# controller16.net
KiCad netlist of a schematic drawn in EAGLE
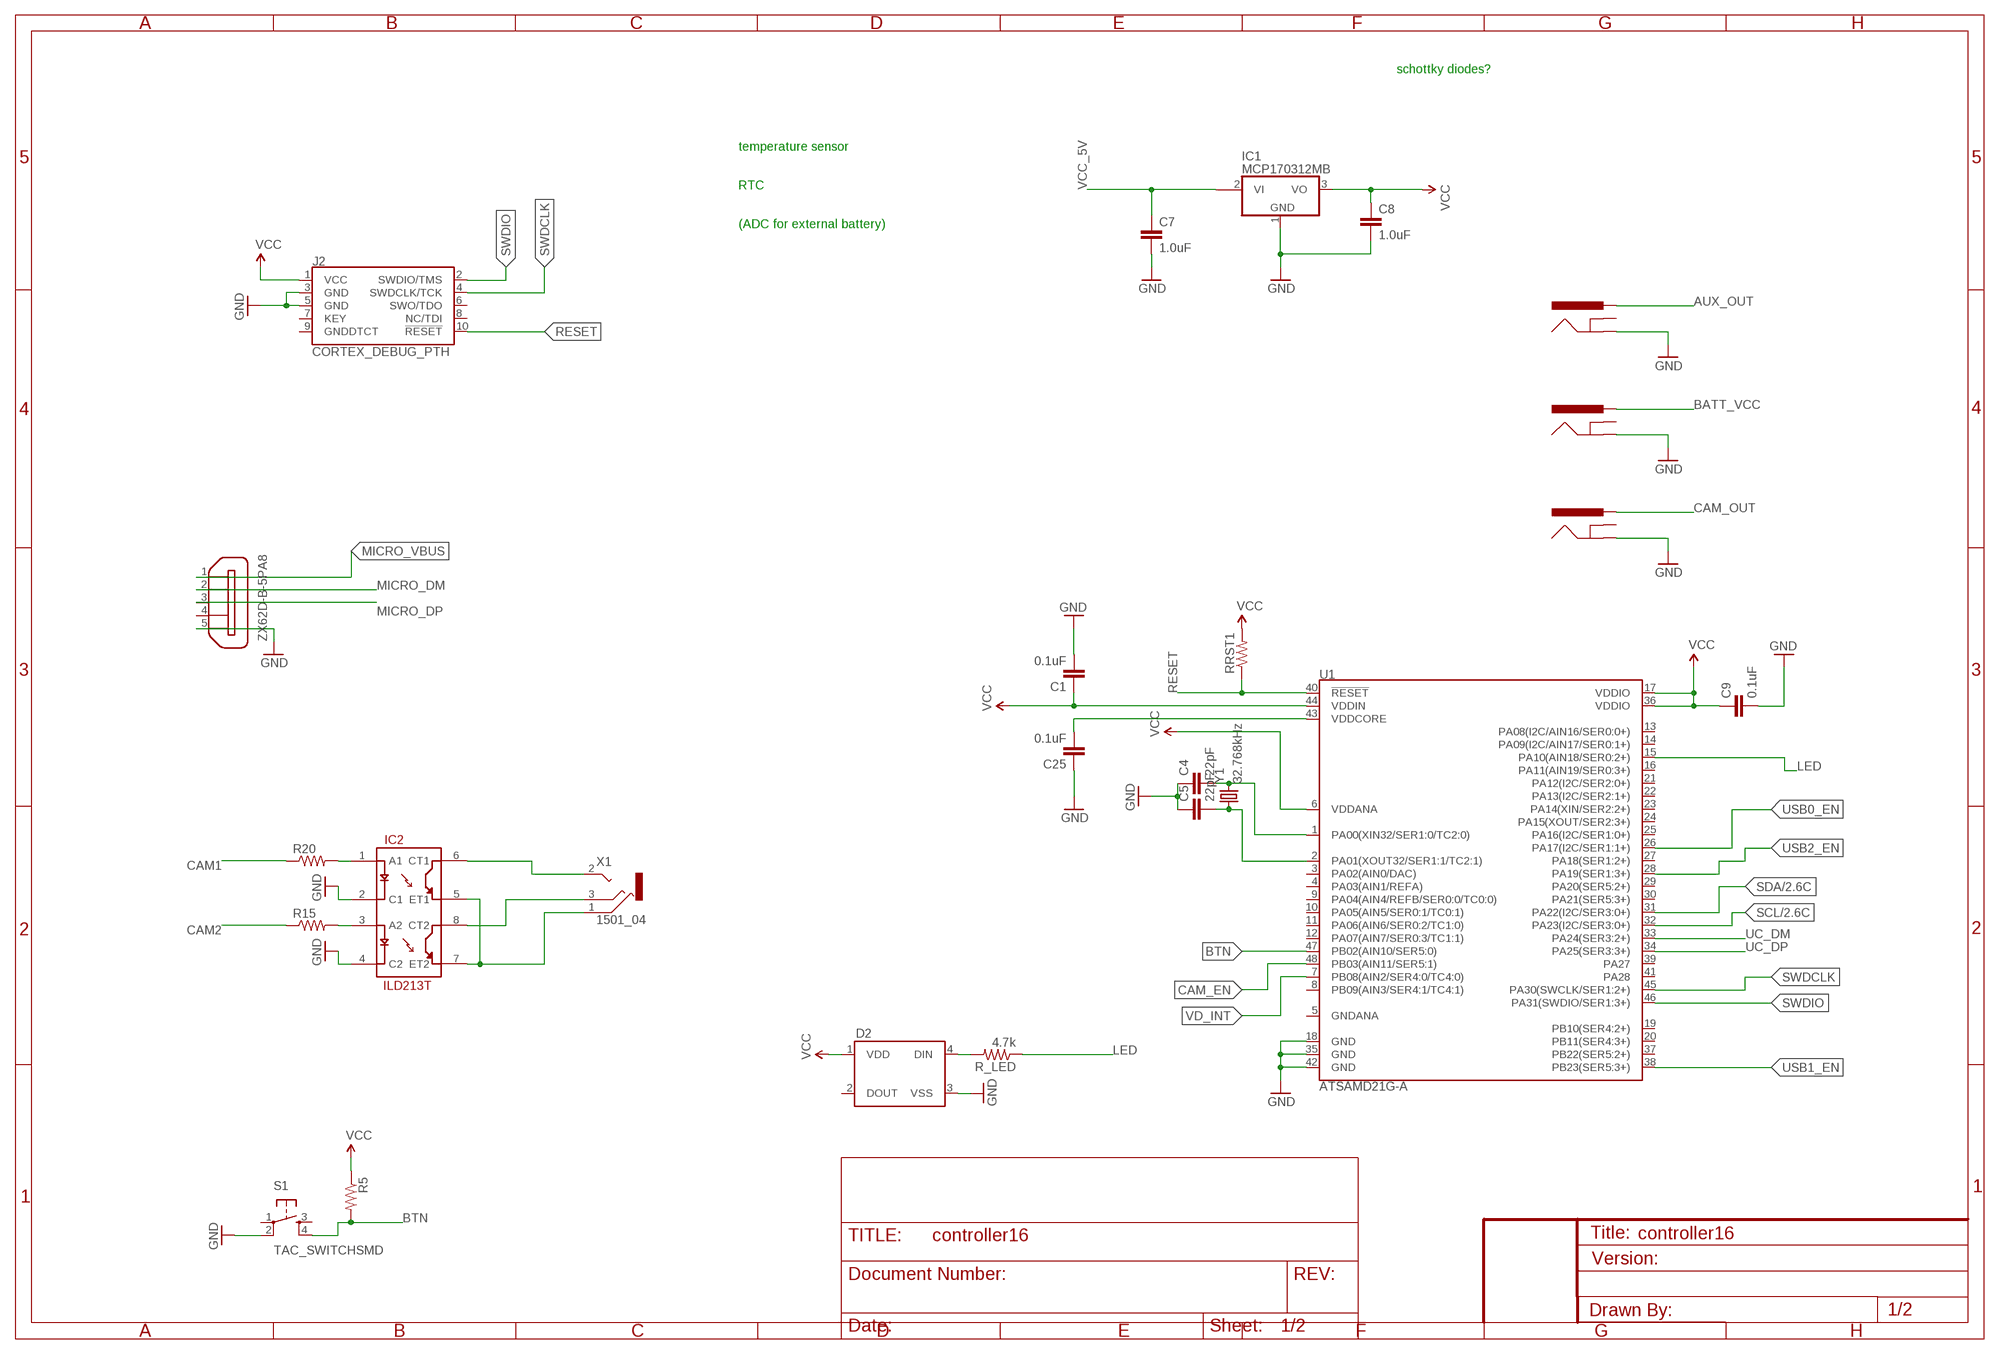
[diagram p0: schematic, sheet 1]
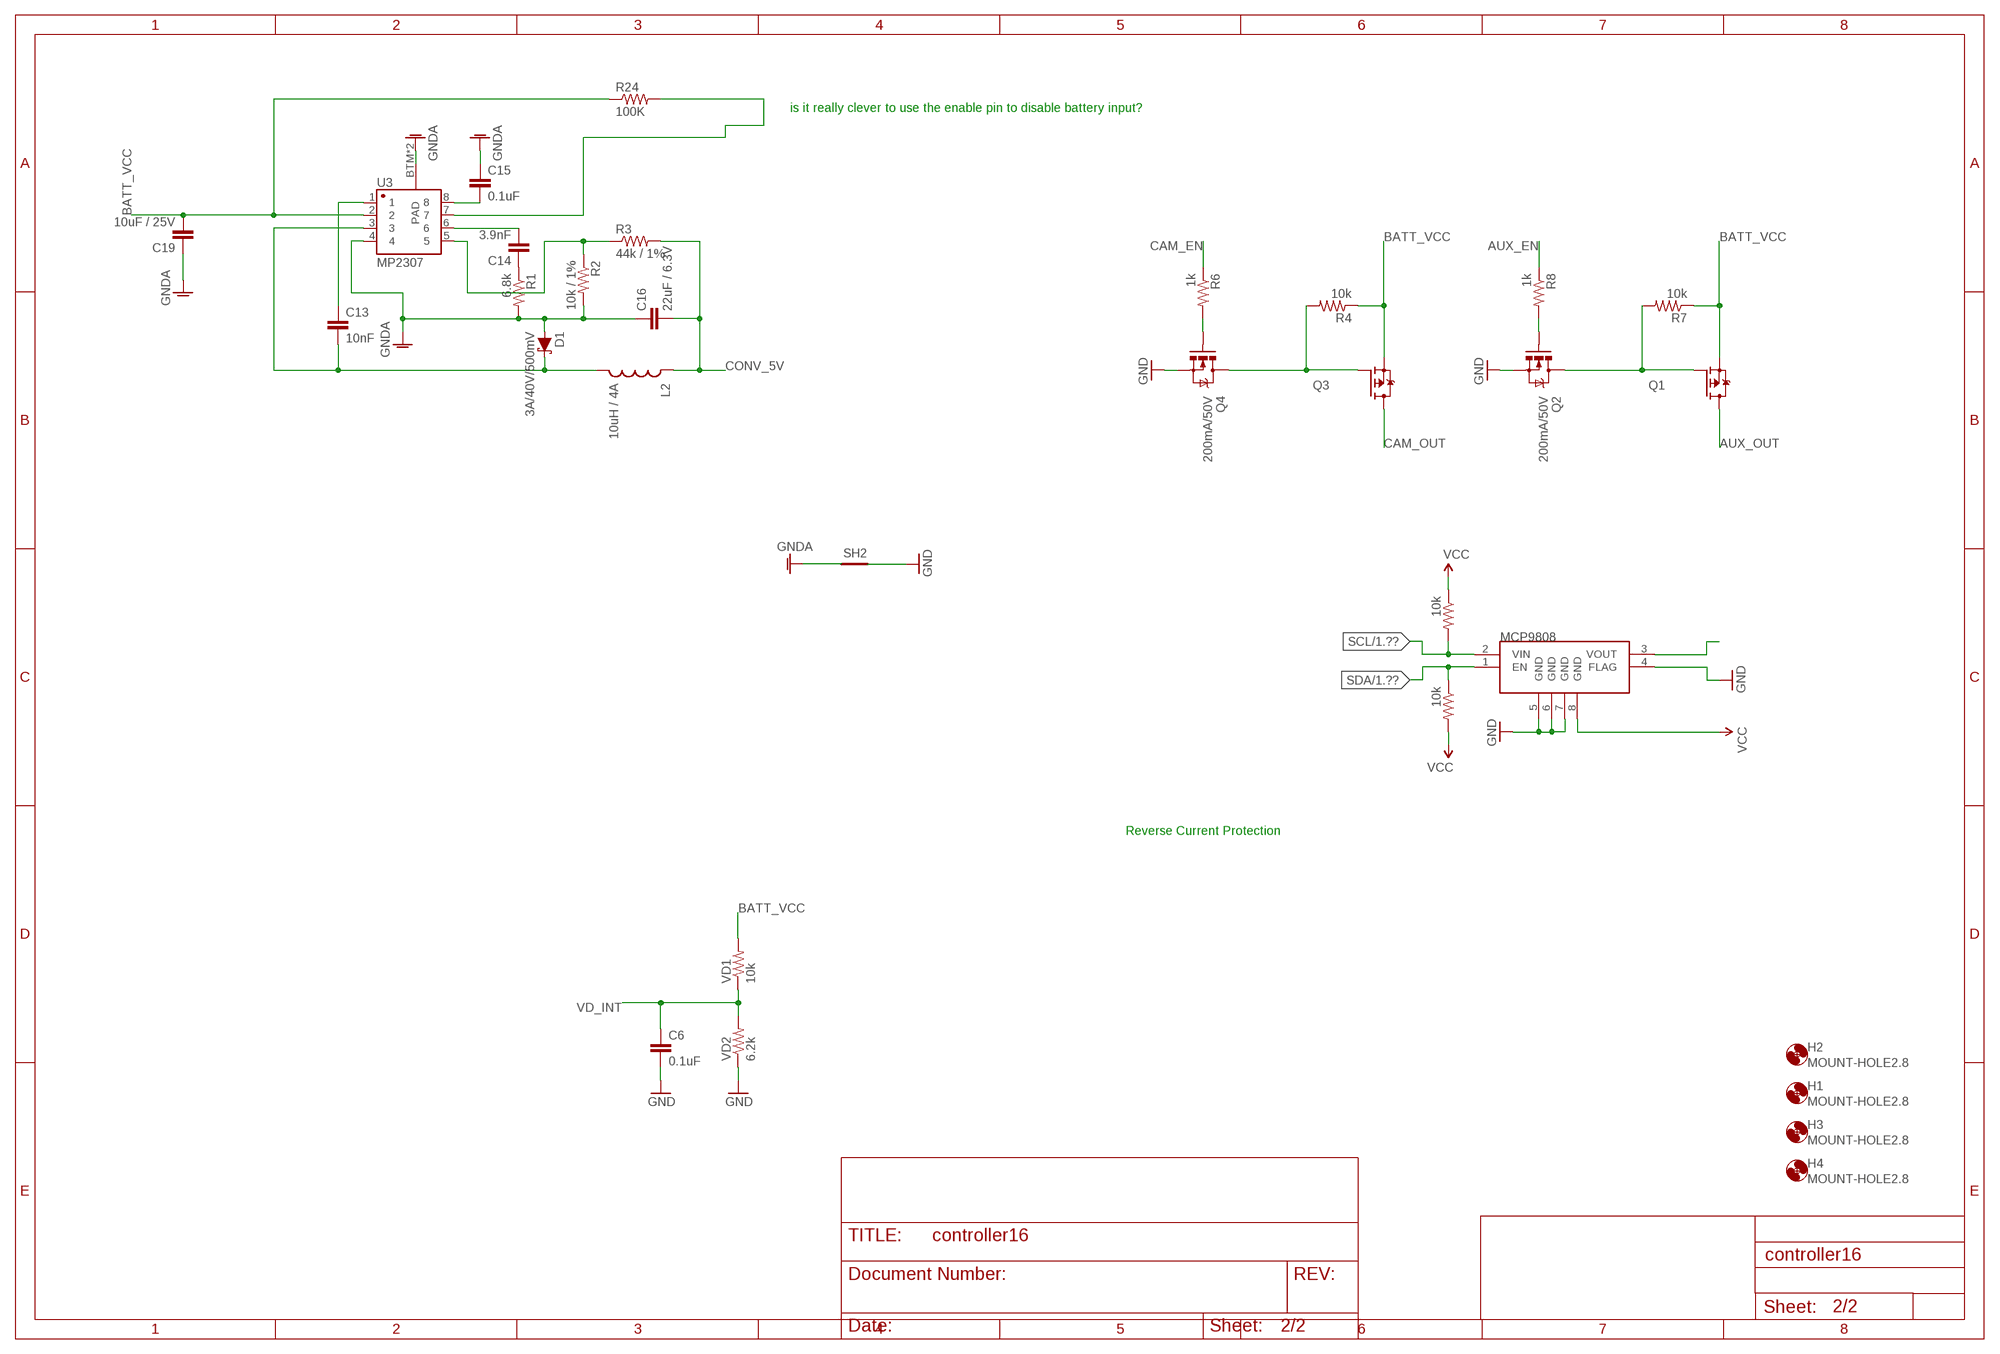
[diagram p1: schematic, sheet 2]

(export (version "E")
  (design (tool "Eeschema 10.0.6"))
  (components
    (comp (ref "C6")
      (value "0.1uF")
      (footprint "eagle-import:1206")
      (libsource (lib "eagle-import") (part "CAP1206"))
    )
    (comp (ref "C13")
      (value "10nF")
      (footprint "eagle-import:0805")
      (libsource (lib "eagle-import") (part "CAP0805"))
    )
    (comp (ref "C14")
      (value "3.9nF")
      (footprint "eagle-import:1206")
      (libsource (lib "eagle-import") (part "CAP1206"))
    )
    (comp (ref "C15")
      (value "0.1uF")
      (footprint "eagle-import:1206")
      (libsource (lib "eagle-import") (part "CAP1206"))
    )
    (comp (ref "C16")
      (value "22uF / 6.3V")
      (footprint "eagle-import:1210")
      (libsource (lib "eagle-import") (part "CAP1210"))
    )
    (comp (ref "C19")
      (value "10uF / 25V")
      (footprint "eagle-import:1210")
      (libsource (lib "eagle-import") (part "CAP1210"))
    )
    (comp (ref "D1")
      (value "3A/40V/500mV")
      (footprint "eagle-import:SMA-DIODE")
      (libsource (lib "eagle-import") (part "DIODE-SCHOTTKY-B340A"))
    )
    (comp (ref "H1")
      (value "MOUNT-HOLE2.8")
      (footprint "eagle-import:2,8")
      (libsource (lib "eagle-import") (part "MOUNT-HOLE2.8"))
    )
    (comp (ref "H2")
      (value "MOUNT-HOLE2.8")
      (footprint "eagle-import:2,8")
      (libsource (lib "eagle-import") (part "MOUNT-HOLE2.8"))
    )
    (comp (ref "H3")
      (value "MOUNT-HOLE2.8")
      (footprint "eagle-import:2,8")
      (libsource (lib "eagle-import") (part "MOUNT-HOLE2.8"))
    )
    (comp (ref "H4")
      (value "MOUNT-HOLE2.8")
      (footprint "eagle-import:2,8")
      (libsource (lib "eagle-import") (part "MOUNT-HOLE2.8"))
    )
    (comp (ref "L2")
      (value "10uH / 4A")
      (footprint "eagle-import:SRU1038")
      (libsource (lib "eagle-import") (part "INDUCTORSRU1038"))
    )
    (comp (ref "MCP9808")
      (value "V_REG_MIC5216")
      (footprint "eagle-import:MSOP8")
      (libsource (lib "eagle-import") (part "V_REG_MIC5216"))
    )
    (comp (ref "Q1")
      (value "FDD4141TO252")
      (footprint "eagle-import:TO252")
      (libsource (lib "eagle-import") (part "FDD4141TO252"))
    )
    (comp (ref "Q2")
      (value "200mA/50V")
      (footprint "eagle-import:SOT23-3")
      (libsource (lib "eagle-import") (part "MOSFET-NCHANNELBSS138"))
    )
    (comp (ref "Q3")
      (value "FDD4141TO252")
      (footprint "eagle-import:TO252")
      (libsource (lib "eagle-import") (part "FDD4141TO252"))
    )
    (comp (ref "Q4")
      (value "200mA/50V")
      (footprint "eagle-import:SOT23-3")
      (libsource (lib "eagle-import") (part "MOSFET-NCHANNELBSS138"))
    )
    (comp (ref "R1")
      (value "6.8k")
      (footprint "eagle-import:1206")
      (libsource (lib "eagle-import") (part "SparkFun-Resistors_RESISTOR1206"))
    )
    (comp (ref "R2")
      (value "10k / 1%")
      (footprint "eagle-import:1206")
      (libsource (lib "eagle-import") (part "SparkFun-Resistors_RESISTOR1206"))
    )
    (comp (ref "R3")
      (value "44k / 1%")
      (footprint "eagle-import:1206")
      (libsource (lib "eagle-import") (part "SparkFun-Resistors_RESISTOR1206"))
    )
    (comp (ref "R4")
      (value "10k")
      (footprint "eagle-import:0805")
      (libsource (lib "eagle-import") (part "SparkFun-Resistors_RESISTOR0805-RES"))
    )
    (comp (ref "R6")
      (value "1k")
      (footprint "eagle-import:0805")
      (libsource (lib "eagle-import") (part "SparkFun-Resistors_RESISTOR0805-RES"))
    )
    (comp (ref "R7")
      (value "10k")
      (footprint "eagle-import:0805")
      (libsource (lib "eagle-import") (part "SparkFun-Resistors_RESISTOR0805-RES"))
    )
    (comp (ref "R8")
      (value "1k")
      (footprint "eagle-import:0805")
      (libsource (lib "eagle-import") (part "SparkFun-Resistors_RESISTOR0805-RES"))
    )
    (comp (ref "R24")
      (value "100K")
      (footprint "eagle-import:1206")
      (libsource (lib "eagle-import") (part "SparkFun-Resistors_RESISTOR1206"))
    )
    (comp (ref "R_I2C_1")
      (value "10k")
      (footprint "eagle-import:0805")
      (libsource (lib "eagle-import") (part "RESISTOR0805-RES"))
    )
    (comp (ref "R_I2C_2")
      (value "10k")
      (footprint "eagle-import:0805")
      (libsource (lib "eagle-import") (part "RESISTOR0805-RES"))
    )
    (comp (ref "SH2")
      (value "SHORT-HT5")
      (footprint "eagle-import:SHORT_TOP-50")
      (libsource (lib "eagle-import") (part "SHORT-HT5"))
    )
    (comp (ref "U3")
      (value "MP2307")
      (footprint "eagle-import:SO08")
      (libsource (lib "eagle-import") (part "GENERIC-SOIC8MSGEQ7N-FILTER"))
    )
    (comp (ref "VD1")
      (value "10k")
      (footprint "eagle-import:1206")
      (libsource (lib "eagle-import") (part "RESISTOR1206"))
    )
    (comp (ref "VD2")
      (value "6.2k")
      (footprint "eagle-import:1206")
      (libsource (lib "eagle-import") (part "RESISTOR1206"))
    )
    (comp (ref "C1")
      (value "0.1uF")
      (footprint "eagle-import:0805")
      (libsource (lib "eagle-import") (part "1.0UF-0805-25V-10%"))
    )
    (comp (ref "C4")
      (value "22pF")
      (footprint "eagle-import:0805")
      (libsource (lib "eagle-import") (part "SparkFun-Passives_CAP0805"))
    )
    (comp (ref "C5")
      (value "22pF")
      (footprint "eagle-import:0805")
      (libsource (lib "eagle-import") (part "SparkFun-Passives_CAP0805"))
    )
    (comp (ref "C7")
      (value "1.0uF")
      (footprint "eagle-import:1206")
      (libsource (lib "eagle-import") (part "1.0UF-1206-50V-10%"))
    )
    (comp (ref "C8")
      (value "1.0uF")
      (footprint "eagle-import:1206")
      (libsource (lib "eagle-import") (part "1.0UF-1206-50V-10%"))
    )
    (comp (ref "C9")
      (value "0.1uF")
      (footprint "eagle-import:0805")
      (libsource (lib "eagle-import") (part "1.0UF-0805-25V-10%"))
    )
    (comp (ref "C25")
      (value "0.1uF")
      (footprint "eagle-import:0805")
      (libsource (lib "eagle-import") (part "1.0UF-0805-25V-10%"))
    )
    (comp (ref "D2")
      (value "WS2812B")
      (footprint "eagle-import:WS2812B")
      (libsource (lib "eagle-import") (part "WS2812B"))
    )
    (comp (ref "IC1")
      (value "MCP170312MB")
      (footprint "eagle-import:SOT89")
      (libsource (lib "eagle-import") (part "MCP1703MB12"))
    )
    (comp (ref "IC2")
      (value "ILD213T")
      (footprint "eagle-import:SO08")
      (libsource (lib "eagle-import") (part "ILD213T"))
    )
    (comp (ref "J1")
      (value "POWER_JACKPTH_BREAD")
      (footprint "eagle-import:POWER_JACK_PTH_BREAD")
      (libsource (lib "eagle-import") (part "POWER_JACKPTH_BREAD"))
    )
    (comp (ref "J2")
      (value "CORTEX_DEBUG_PTH")
      (footprint "eagle-import:2X5-PTH-1.27MM")
      (libsource (lib "eagle-import") (part "CORTEX_DEBUG_PTH"))
    )
    (comp (ref "J3")
      (value "POWER_JACKPTH_BREAD")
      (footprint "eagle-import:POWER_JACK_PTH_BREAD")
      (libsource (lib "eagle-import") (part "POWER_JACKPTH_BREAD"))
    )
    (comp (ref "J4")
      (value "POWER_JACKPTH_BREAD")
      (footprint "eagle-import:POWER_JACK_PTH_BREAD")
      (libsource (lib "eagle-import") (part "POWER_JACKPTH_BREAD"))
    )
    (comp (ref "R5")
      (value "RESISTOR0805-RES")
      (footprint "eagle-import:0805")
      (libsource (lib "eagle-import") (part "RESISTOR0805-RES"))
    )
    (comp (ref "R15")
      (value "RESISTOR0805-RES")
      (footprint "eagle-import:0805")
      (libsource (lib "eagle-import") (part "RESISTOR0805-RES"))
    )
    (comp (ref "R20")
      (value "RESISTOR0805-RES")
      (footprint "eagle-import:0805")
      (libsource (lib "eagle-import") (part "RESISTOR0805-RES"))
    )
    (comp (ref "RRST1")
      (value "RESISTOR0805-RES")
      (footprint "eagle-import:0805")
      (libsource (lib "eagle-import") (part "RESISTOR0805-RES"))
    )
    (comp (ref "R_LED")
      (value "4.7k")
      (footprint "eagle-import:0805")
      (libsource (lib "eagle-import") (part "SparkFun-Resistors_RESISTOR0805-RES"))
    )
    (comp (ref "S1")
      (value "TAC_SWITCHSMD")
      (footprint "eagle-import:TACTILE-SWITCH-SMD")
      (libsource (lib "eagle-import") (part "TAC_SWITCHSMD"))
    )
    (comp (ref "U1")
      (value "ATSAMD21G-A")
      (footprint "eagle-import:TQFP-48")
      (libsource (lib "eagle-import") (part "ATSAMD21G-A"))
    )
    (comp (ref "X1")
      (value "1501_04")
      (footprint "eagle-import:1501_05")
      (libsource (lib "eagle-import") (part "1501_04"))
    )
    (comp (ref "X2")
      (value "ZX62D-B-5PA8")
      (footprint "eagle-import:ZX62D-B-5PA8")
      (fields (field (name "MF") "Hirose"))
      (libsource (lib "eagle-import") (part "ZX62D-B-5PA8"))
    )
    (comp (ref "Y1")
      (value "32.768kHz")
      (footprint "eagle-import:CRYSTAL-SMD-3.2X1.5MM")
      (libsource (lib "eagle-import") (part "CRYSTAL3.2X1.5MM"))
    )
  )
  (nets
    (net (code "1") (name "AUX_EN") (class "Default")
      (node (ref "R8") (pin "1") (pinfunction "1_1") (pintype "passive"))
    )
    (net (code "2") (name "AUX_OUT") (class "Default")
      (node (ref "J1") (pin "PWR") (pinfunction "PWR_PWR") (pintype "bidirectional"))
      (node (ref "Q1") (pin "3") (pinfunction "D_3") (pintype "passive"))
    )
    (net (code "3") (name "BATT_VCC") (class "Default")
      (node (ref "C19") (pin "2") (pinfunction "2_2") (pintype "passive"))
      (node (ref "J4") (pin "PWR") (pinfunction "PWR_PWR") (pintype "bidirectional"))
      (node (ref "Q1") (pin "2") (pinfunction "S_2") (pintype "passive"))
      (node (ref "Q3") (pin "2") (pinfunction "S_2") (pintype "passive"))
      (node (ref "R24") (pin "1") (pinfunction "1_1") (pintype "passive"))
      (node (ref "R4") (pin "1") (pinfunction "1_1") (pintype "passive"))
      (node (ref "R7") (pin "1") (pinfunction "1_1") (pintype "passive"))
      (node (ref "U3") (pin "2") (pinfunction "2_2") (pintype "bidirectional"))
      (node (ref "VD1") (pin "2") (pinfunction "2_2") (pintype "passive"))
    )
    (net (code "4") (name "BTN") (class "Default")
      (node (ref "R5") (pin "2") (pinfunction "2_2") (pintype "passive"))
      (node (ref "S1") (pin "4") (pinfunction "4_4") (pintype "passive"))
      (node (ref "U1") (pin "47") (pinfunction "PB02(AIN10/SER5:0)_47") (pintype "bidirectional"))
    )
    (net (code "5") (name "CAM1") (class "Default")
      (node (ref "R20") (pin "1") (pinfunction "1_1") (pintype "passive"))
    )
    (net (code "6") (name "CAM2") (class "Default")
      (node (ref "R15") (pin "1") (pinfunction "1_1") (pintype "passive"))
    )
    (net (code "7") (name "CAM_EN") (class "Default")
      (node (ref "R6") (pin "1") (pinfunction "1_1") (pintype "passive"))
      (node (ref "U1") (pin "48") (pinfunction "PB03(AIN11/SER5:1)_48") (pintype "bidirectional"))
    )
    (net (code "8") (name "CAM_OUT") (class "Default")
      (node (ref "J3") (pin "PWR") (pinfunction "PWR_PWR") (pintype "bidirectional"))
      (node (ref "Q3") (pin "3") (pinfunction "D_3") (pintype "passive"))
    )
    (net (code "9") (name "CONV_5V") (class "Default")
      (node (ref "C16") (pin "2") (pinfunction "2_2") (pintype "passive"))
      (node (ref "L2") (pin "1") (pinfunction "1_1") (pintype "passive"))
      (node (ref "R3") (pin "2") (pinfunction "2_2") (pintype "passive"))
    )
    (net (code "10") (name "GND") (class "Default")
      (node (ref "C1") (pin "2") (pinfunction "2_2") (pintype "passive"))
      (node (ref "C25") (pin "1") (pinfunction "1_1") (pintype "passive"))
      (node (ref "C4") (pin "1") (pinfunction "1_1") (pintype "passive"))
      (node (ref "C5") (pin "1") (pinfunction "1_1") (pintype "passive"))
      (node (ref "C6") (pin "2") (pinfunction "2_2") (pintype "passive"))
      (node (ref "C7") (pin "2") (pinfunction "2_2") (pintype "passive"))
      (node (ref "C8") (pin "2") (pinfunction "2_2") (pintype "passive"))
      (node (ref "C9") (pin "2") (pinfunction "2_2") (pintype "passive"))
      (node (ref "D2") (pin "3") (pinfunction "VSS_3") (pintype "power_in"))
      (node (ref "IC1") (pin "1") (pinfunction "GND_1") (pintype "passive"))
      (node (ref "IC2") (pin "2") (pinfunction "C1_2") (pintype "bidirectional"))
      (node (ref "IC2") (pin "4") (pinfunction "C2_4") (pintype "bidirectional"))
      (node (ref "J1") (pin "GND") (pinfunction "GND_GND") (pintype "bidirectional"))
      (node (ref "J2") (pin "3") (pinfunction "GND_3") (pintype "bidirectional"))
      (node (ref "J2") (pin "5") (pinfunction "GND_5") (pintype "bidirectional"))
      (node (ref "J3") (pin "GND") (pinfunction "GND_GND") (pintype "bidirectional"))
      (node (ref "J4") (pin "GND") (pinfunction "GND_GND") (pintype "bidirectional"))
      (node (ref "MCP9808") (pin "4") (pinfunction "FLAG_4") (pintype "bidirectional"))
      (node (ref "MCP9808") (pin "5") (pinfunction "GND_5") (pintype "bidirectional"))
      (node (ref "MCP9808") (pin "6") (pinfunction "GND_6") (pintype "bidirectional"))
      (node (ref "MCP9808") (pin "7") (pinfunction "GND_7") (pintype "bidirectional"))
      (node (ref "Q2") (pin "2") (pinfunction "S_2") (pintype "passive"))
      (node (ref "Q4") (pin "2") (pinfunction "S_2") (pintype "passive"))
      (node (ref "S1") (pin "2") (pinfunction "2_2") (pintype "passive"))
      (node (ref "SH2") (pin "2") (pinfunction "P$2_2") (pintype "bidirectional"))
      (node (ref "U1") (pin "18") (pinfunction "GND_18") (pintype "bidirectional"))
      (node (ref "U1") (pin "35") (pinfunction "GND_35") (pintype "bidirectional"))
      (node (ref "U1") (pin "42") (pinfunction "GND_42") (pintype "bidirectional"))
      (node (ref "VD2") (pin "1") (pinfunction "1_1") (pintype "passive"))
      (node (ref "X2") (pin "5") (pinfunction "5_5") (pintype "passive"))
    )
    (net (code "11") (name "GNDA") (class "Default")
      (node (ref "C15") (pin "1") (pinfunction "1_1") (pintype "passive"))
      (node (ref "C16") (pin "1") (pinfunction "1_1") (pintype "passive"))
      (node (ref "C19") (pin "1") (pinfunction "1_1") (pintype "passive"))
      (node (ref "D1") (pin "A") (pinfunction "A_A") (pintype "passive"))
      (node (ref "R1") (pin "2") (pinfunction "2_2") (pintype "passive"))
      (node (ref "R2") (pin "2") (pinfunction "2_2") (pintype "passive"))
      (node (ref "SH2") (pin "1") (pinfunction "P$1_1") (pintype "bidirectional"))
      (node (ref "U3") (pin "4") (pinfunction "4_4") (pintype "bidirectional"))
      (node (ref "U3") (pin "BTM") (pinfunction "PAD_BTM") (pintype "bidirectional"))
      (node (ref "U3") (pin "P$1") (pinfunction "PAD_P$1") (pintype "bidirectional"))
    )
    (net (code "12") (name "LED") (class "Default")
      (node (ref "R_LED") (pin "1") (pinfunction "1_1") (pintype "passive"))
      (node (ref "U1") (pin "15") (pinfunction "PA10(AIN18/SER0:2+)_15") (pintype "bidirectional"))
    )
    (net (code "13") (name "MICRO_DM") (class "Default")
      (node (ref "X2") (pin "2") (pinfunction "2_2") (pintype "passive"))
    )
    (net (code "14") (name "MICRO_DP") (class "Default")
      (node (ref "X2") (pin "3") (pinfunction "3_3") (pintype "passive"))
    )
    (net (code "15") (name "MICRO_VBUS") (class "Default")
      (node (ref "X2") (pin "1") (pinfunction "1_1") (pintype "passive"))
    )
    (net (code "16") (name "Net-(C13-Pad1)") (class "Default")
      (node (ref "C13") (pin "1") (pinfunction "1_1") (pintype "passive"))
      (node (ref "U3") (pin "1") (pinfunction "1_1") (pintype "bidirectional"))
    )
    (net (code "17") (name "Net-(C13-Pad2)") (class "Default")
      (node (ref "C13") (pin "2") (pinfunction "2_2") (pintype "passive"))
      (node (ref "D1") (pin "C") (pinfunction "C_C") (pintype "passive"))
      (node (ref "L2") (pin "2") (pinfunction "2_2") (pintype "passive"))
      (node (ref "U3") (pin "3") (pinfunction "3_3") (pintype "bidirectional"))
    )
    (net (code "18") (name "Net-(C14-Pad1)") (class "Default")
      (node (ref "C14") (pin "1") (pinfunction "1_1") (pintype "passive"))
      (node (ref "R1") (pin "1") (pinfunction "1_1") (pintype "passive"))
    )
    (net (code "19") (name "Net-(C14-Pad2)") (class "Default")
      (node (ref "C14") (pin "2") (pinfunction "2_2") (pintype "passive"))
      (node (ref "U3") (pin "6") (pinfunction "6_6") (pintype "bidirectional"))
    )
    (net (code "20") (name "Net-(C15-Pad2)") (class "Default")
      (node (ref "C15") (pin "2") (pinfunction "2_2") (pintype "passive"))
      (node (ref "U3") (pin "8") (pinfunction "8_8") (pintype "bidirectional"))
    )
    (net (code "21") (name "Net-(D2-DIN)") (class "Default")
      (node (ref "D2") (pin "4") (pinfunction "DIN_4") (pintype "input"))
      (node (ref "R_LED") (pin "2") (pinfunction "2_2") (pintype "passive"))
    )
    (net (code "22") (name "Net-(IC2-A1)") (class "Default")
      (node (ref "IC2") (pin "1") (pinfunction "A1_1") (pintype "bidirectional"))
      (node (ref "R20") (pin "2") (pinfunction "2_2") (pintype "passive"))
    )
    (net (code "23") (name "Net-(IC2-A2)") (class "Default")
      (node (ref "IC2") (pin "3") (pinfunction "A2_3") (pintype "bidirectional"))
      (node (ref "R15") (pin "2") (pinfunction "2_2") (pintype "passive"))
    )
    (net (code "24") (name "Net-(IC2-CT1)") (class "Default")
      (node (ref "IC2") (pin "6") (pinfunction "CT1_6") (pintype "bidirectional"))
      (node (ref "X1") (pin "2") (pinfunction "2_2") (pintype "passive"))
    )
    (net (code "25") (name "Net-(IC2-CT2)") (class "Default")
      (node (ref "IC2") (pin "8") (pinfunction "CT2_8") (pintype "bidirectional"))
      (node (ref "X1") (pin "3") (pinfunction "3_3") (pintype "passive"))
    )
    (net (code "26") (name "Net-(IC2-ET1)") (class "Default")
      (node (ref "IC2") (pin "5") (pinfunction "ET1_5") (pintype "bidirectional"))
      (node (ref "IC2") (pin "7") (pinfunction "ET2_7") (pintype "bidirectional"))
      (node (ref "X1") (pin "1") (pinfunction "1_1") (pintype "passive"))
    )
    (net (code "27") (name "Net-(Q1-G)") (class "Default")
      (node (ref "Q1") (pin "1") (pinfunction "G_1") (pintype "passive"))
      (node (ref "Q2") (pin "3") (pinfunction "D_3") (pintype "passive"))
      (node (ref "R7") (pin "2") (pinfunction "2_2") (pintype "passive"))
    )
    (net (code "28") (name "Net-(Q2-G)") (class "Default")
      (node (ref "Q2") (pin "1") (pinfunction "G_1") (pintype "passive"))
      (node (ref "R8") (pin "2") (pinfunction "2_2") (pintype "passive"))
    )
    (net (code "29") (name "Net-(Q3-G)") (class "Default")
      (node (ref "Q3") (pin "1") (pinfunction "G_1") (pintype "passive"))
      (node (ref "Q4") (pin "3") (pinfunction "D_3") (pintype "passive"))
      (node (ref "R4") (pin "2") (pinfunction "2_2") (pintype "passive"))
    )
    (net (code "30") (name "Net-(Q4-G)") (class "Default")
      (node (ref "Q4") (pin "1") (pinfunction "G_1") (pintype "passive"))
      (node (ref "R6") (pin "2") (pinfunction "2_2") (pintype "passive"))
    )
    (net (code "31") (name "Net-(R2-Pad1)") (class "Default")
      (node (ref "R2") (pin "1") (pinfunction "1_1") (pintype "passive"))
      (node (ref "R3") (pin "1") (pinfunction "1_1") (pintype "passive"))
      (node (ref "U3") (pin "5") (pinfunction "5_5") (pintype "bidirectional"))
    )
    (net (code "32") (name "Net-(R24-Pad2)") (class "Default")
      (node (ref "R24") (pin "2") (pinfunction "2_2") (pintype "passive"))
      (node (ref "U3") (pin "7") (pinfunction "7_7") (pintype "bidirectional"))
    )
    (net (code "33") (name "Net-(U1-PA00(XIN32{slash}SER1:0{slash}TC2:0))") (class "Default")
      (node (ref "C4") (pin "2") (pinfunction "2_2") (pintype "passive"))
      (node (ref "U1") (pin "1") (pinfunction "PA00(XIN32/SER1:0/TC2:0)_1") (pintype "bidirectional"))
      (node (ref "Y1") (pin "P$2") (pinfunction "2_P$2") (pintype "passive"))
    )
    (net (code "34") (name "Net-(U1-PA01(XOUT32{slash}SER1:1{slash}TC2:1))") (class "Default")
      (node (ref "C5") (pin "2") (pinfunction "2_2") (pintype "passive"))
      (node (ref "U1") (pin "2") (pinfunction "PA01(XOUT32/SER1:1/TC2:1)_2") (pintype "bidirectional"))
      (node (ref "Y1") (pin "P$1") (pinfunction "1_P$1") (pintype "passive"))
    )
    (net (code "35") (name "Net-(U1-VDDCORE)") (class "Default")
      (node (ref "C25") (pin "2") (pinfunction "2_2") (pintype "passive"))
      (node (ref "U1") (pin "43") (pinfunction "VDDCORE_43") (pintype "bidirectional"))
    )
    (net (code "36") (name "RESET") (class "Default")
      (node (ref "J2") (pin "10") (pinfunction "~{RESET}_10") (pintype "bidirectional"))
      (node (ref "RRST1") (pin "1") (pinfunction "1_1") (pintype "passive"))
      (node (ref "U1") (pin "40") (pinfunction "~{RESET}_40") (pintype "bidirectional"))
    )
    (net (code "37") (name "SCL") (class "Default")
      (node (ref "MCP9808") (pin "2") (pinfunction "VIN_2") (pintype "bidirectional"))
      (node (ref "R_I2C_1") (pin "2") (pinfunction "2_2") (pintype "passive"))
      (node (ref "U1") (pin "32") (pinfunction "PA23(I2C/SER3:0+)_32") (pintype "bidirectional"))
    )
    (net (code "38") (name "SDA") (class "Default")
      (node (ref "MCP9808") (pin "1") (pinfunction "EN_1") (pintype "bidirectional"))
      (node (ref "R_I2C_2") (pin "1") (pinfunction "1_1") (pintype "passive"))
      (node (ref "U1") (pin "31") (pinfunction "PA22(I2C/SER3:0+)_31") (pintype "bidirectional"))
    )
    (net (code "39") (name "SWDCLK") (class "Default")
      (node (ref "J2") (pin "4") (pinfunction "SWDCLK/TCK_4") (pintype "bidirectional"))
      (node (ref "U1") (pin "45") (pinfunction "PA30(SWCLK/SER1:2+)_45") (pintype "bidirectional"))
    )
    (net (code "40") (name "SWDIO") (class "Default")
      (node (ref "J2") (pin "2") (pinfunction "SWDIO/TMS_2") (pintype "bidirectional"))
      (node (ref "U1") (pin "46") (pinfunction "PA31(SWDIO/SER1:3+)_46") (pintype "bidirectional"))
    )
    (net (code "41") (name "UC_DM") (class "Default")
      (node (ref "U1") (pin "33") (pinfunction "PA24(SER3:2+)_33") (pintype "bidirectional"))
    )
    (net (code "42") (name "UC_DP") (class "Default")
      (node (ref "U1") (pin "34") (pinfunction "PA25(SER3:3+)_34") (pintype "bidirectional"))
    )
    (net (code "43") (name "USB0_EN") (class "Default")
      (node (ref "U1") (pin "26") (pinfunction "PA17(I2C/SER1:1+)_26") (pintype "bidirectional"))
    )
    (net (code "44") (name "USB1_EN") (class "Default")
      (node (ref "U1") (pin "38") (pinfunction "PB23(SER5:3+)_38") (pintype "bidirectional"))
    )
    (net (code "45") (name "USB2_EN") (class "Default")
      (node (ref "U1") (pin "28") (pinfunction "PA19(SER1:3+)_28") (pintype "bidirectional"))
    )
    (net (code "46") (name "VCC") (class "Default")
      (node (ref "C1") (pin "1") (pinfunction "1_1") (pintype "passive"))
      (node (ref "C8") (pin "1") (pinfunction "1_1") (pintype "passive"))
      (node (ref "C9") (pin "1") (pinfunction "1_1") (pintype "passive"))
      (node (ref "D2") (pin "1") (pinfunction "VDD_1") (pintype "power_in"))
      (node (ref "IC1") (pin "3") (pinfunction "VO_3") (pintype "passive"))
      (node (ref "J2") (pin "1") (pinfunction "VCC_1") (pintype "bidirectional"))
      (node (ref "MCP9808") (pin "8") (pinfunction "GND_8") (pintype "bidirectional"))
      (node (ref "R5") (pin "1") (pinfunction "1_1") (pintype "passive"))
      (node (ref "RRST1") (pin "2") (pinfunction "2_2") (pintype "passive"))
      (node (ref "R_I2C_1") (pin "1") (pinfunction "1_1") (pintype "passive"))
      (node (ref "R_I2C_2") (pin "2") (pinfunction "2_2") (pintype "passive"))
      (node (ref "U1") (pin "17") (pinfunction "VDDIO_17") (pintype "bidirectional"))
      (node (ref "U1") (pin "36") (pinfunction "VDDIO_36") (pintype "bidirectional"))
      (node (ref "U1") (pin "44") (pinfunction "VDDIN_44") (pintype "bidirectional"))
      (node (ref "U1") (pin "6") (pinfunction "VDDANA_6") (pintype "bidirectional"))
    )
    (net (code "47") (name "VCC_5V") (class "Default")
      (node (ref "C7") (pin "1") (pinfunction "1_1") (pintype "passive"))
      (node (ref "IC1") (pin "2@1") (pinfunction "VI1_2@1") (pintype "input"))
    )
    (net (code "48") (name "VD_INT") (class "Default")
      (node (ref "C6") (pin "1") (pinfunction "1_1") (pintype "passive"))
      (node (ref "U1") (pin "7") (pinfunction "PB08(AIN2/SER4:0/TC4:0)_7") (pintype "bidirectional"))
      (node (ref "VD1") (pin "1") (pinfunction "1_1") (pintype "passive"))
      (node (ref "VD2") (pin "2") (pinfunction "2_2") (pintype "passive"))
    )
    (net (code "49") (name "unconnected-(D2-DOUT-Pad2)") (class "Default")
      (node (ref "D2") (pin "2") (pinfunction "DOUT_2") (pintype "output"))
    )
    (net (code "50") (name "unconnected-(IC1-VI-Pad2)") (class "Default")
      (node (ref "IC1") (pin "2") (pinfunction "VI_2") (pintype "input"))
    )
    (net (code "51") (name "unconnected-(J1-PadGNDBREAK)") (class "Default")
      (node (ref "J1") (pin "GNDBREAK") (pinfunction "GNDBREAK_GNDBREAK") (pintype "bidirectional"))
    )
    (net (code "52") (name "unconnected-(J2-GNDDTCT-Pad9)") (class "Default")
      (node (ref "J2") (pin "9") (pinfunction "GNDDTCT_9") (pintype "bidirectional"))
    )
    (net (code "53") (name "unconnected-(J2-KEY-Pad7)") (class "Default")
      (node (ref "J2") (pin "7") (pinfunction "KEY_7") (pintype "bidirectional"))
    )
    (net (code "54") (name "unconnected-(J2-NC{slash}TDI-Pad8)") (class "Default")
      (node (ref "J2") (pin "8") (pinfunction "NC/TDI_8") (pintype "bidirectional"))
    )
    (net (code "55") (name "unconnected-(J2-SWO{slash}TDO-Pad6)") (class "Default")
      (node (ref "J2") (pin "6") (pinfunction "SWO/TDO_6") (pintype "bidirectional"))
    )
    (net (code "56") (name "unconnected-(J3-PadGNDBREAK)") (class "Default")
      (node (ref "J3") (pin "GNDBREAK") (pinfunction "GNDBREAK_GNDBREAK") (pintype "bidirectional"))
    )
    (net (code "57") (name "unconnected-(J4-PadGNDBREAK)") (class "Default")
      (node (ref "J4") (pin "GNDBREAK") (pinfunction "GNDBREAK_GNDBREAK") (pintype "bidirectional"))
    )
    (net (code "58") (name "unconnected-(MCP9808-VOUT-Pad3)") (class "Default")
      (node (ref "MCP9808") (pin "3") (pinfunction "VOUT_3") (pintype "bidirectional"))
    )
    (net (code "59") (name "unconnected-(S1-Pad1)") (class "Default")
      (node (ref "S1") (pin "1") (pinfunction "1_1") (pintype "passive"))
    )
    (net (code "60") (name "unconnected-(S1-Pad3)") (class "Default")
      (node (ref "S1") (pin "3") (pinfunction "3_3") (pintype "passive"))
    )
    (net (code "61") (name "unconnected-(U1-GNDANA-Pad5)") (class "Default")
      (node (ref "U1") (pin "5") (pinfunction "GNDANA_5") (pintype "bidirectional"))
    )
    (net (code "62") (name "unconnected-(U1-PA02(AIN0{slash}DAC)-Pad3)") (class "Default")
      (node (ref "U1") (pin "3") (pinfunction "PA02(AIN0/DAC)_3") (pintype "bidirectional"))
    )
    (net (code "63") (name "unconnected-(U1-PA03(AIN1{slash}REFA)-Pad4)") (class "Default")
      (node (ref "U1") (pin "4") (pinfunction "PA03(AIN1/REFA)_4") (pintype "bidirectional"))
    )
    (net (code "64") (name "unconnected-(U1-PA04(AIN4{slash}REFB{slash}SER0:0{slash}TC0:0)-Pad9)") (class "Default")
      (node (ref "U1") (pin "9") (pinfunction "PA04(AIN4/REFB/SER0:0/TC0:0)_9") (pintype "bidirectional"))
    )
    (net (code "65") (name "unconnected-(U1-PA05(AIN5{slash}SER0:1{slash}TC0:1)-Pad10)") (class "Default")
      (node (ref "U1") (pin "10") (pinfunction "PA05(AIN5/SER0:1/TC0:1)_10") (pintype "bidirectional"))
    )
    (net (code "66") (name "unconnected-(U1-PA06(AIN6{slash}SER0:2{slash}TC1:0)-Pad11)") (class "Default")
      (node (ref "U1") (pin "11") (pinfunction "PA06(AIN6/SER0:2/TC1:0)_11") (pintype "bidirectional"))
    )
    (net (code "67") (name "unconnected-(U1-PA07(AIN7{slash}SER0:3{slash}TC1:1)-Pad12)") (class "Default")
      (node (ref "U1") (pin "12") (pinfunction "PA07(AIN7/SER0:3/TC1:1)_12") (pintype "bidirectional"))
    )
    (net (code "68") (name "unconnected-(U1-PA08(I2C{slash}AIN16{slash}SER0:0+)-Pad13)") (class "Default")
      (node (ref "U1") (pin "13") (pinfunction "PA08(I2C/AIN16/SER0:0+)_13") (pintype "bidirectional"))
    )
    (net (code "69") (name "unconnected-(U1-PA09(I2C{slash}AIN17{slash}SER0:1+)-Pad14)") (class "Default")
      (node (ref "U1") (pin "14") (pinfunction "PA09(I2C/AIN17/SER0:1+)_14") (pintype "bidirectional"))
    )
    (net (code "70") (name "unconnected-(U1-PA11(AIN19{slash}SER0:3+)-Pad16)") (class "Default")
      (node (ref "U1") (pin "16") (pinfunction "PA11(AIN19/SER0:3+)_16") (pintype "bidirectional"))
    )
    (net (code "71") (name "unconnected-(U1-PA12(I2C{slash}SER2:0+)-Pad21)") (class "Default")
      (node (ref "U1") (pin "21") (pinfunction "PA12(I2C/SER2:0+)_21") (pintype "bidirectional"))
    )
    (net (code "72") (name "unconnected-(U1-PA13(I2C{slash}SER2:1+)-Pad22)") (class "Default")
      (node (ref "U1") (pin "22") (pinfunction "PA13(I2C/SER2:1+)_22") (pintype "bidirectional"))
    )
    (net (code "73") (name "unconnected-(U1-PA14(XIN{slash}SER2:2+)-Pad23)") (class "Default")
      (node (ref "U1") (pin "23") (pinfunction "PA14(XIN/SER2:2+)_23") (pintype "bidirectional"))
    )
    (net (code "74") (name "unconnected-(U1-PA15(XOUT{slash}SER2:3+)-Pad24)") (class "Default")
      (node (ref "U1") (pin "24") (pinfunction "PA15(XOUT/SER2:3+)_24") (pintype "bidirectional"))
    )
    (net (code "75") (name "unconnected-(U1-PA16(I2C{slash}SER1:0+)-Pad25)") (class "Default")
      (node (ref "U1") (pin "25") (pinfunction "PA16(I2C/SER1:0+)_25") (pintype "bidirectional"))
    )
    (net (code "76") (name "unconnected-(U1-PA18(SER1:2+)-Pad27)") (class "Default")
      (node (ref "U1") (pin "27") (pinfunction "PA18(SER1:2+)_27") (pintype "bidirectional"))
    )
    (net (code "77") (name "unconnected-(U1-PA20(SER5:2+)-Pad29)") (class "Default")
      (node (ref "U1") (pin "29") (pinfunction "PA20(SER5:2+)_29") (pintype "bidirectional"))
    )
    (net (code "78") (name "unconnected-(U1-PA21(SER5:3+)-Pad30)") (class "Default")
      (node (ref "U1") (pin "30") (pinfunction "PA21(SER5:3+)_30") (pintype "bidirectional"))
    )
    (net (code "79") (name "unconnected-(U1-PA27-Pad39)") (class "Default")
      (node (ref "U1") (pin "39") (pinfunction "PA27_39") (pintype "bidirectional"))
    )
    (net (code "80") (name "unconnected-(U1-PA28-Pad41)") (class "Default")
      (node (ref "U1") (pin "41") (pinfunction "PA28_41") (pintype "bidirectional"))
    )
    (net (code "81") (name "unconnected-(U1-PB09(AIN3{slash}SER4:1{slash}TC4:1)-Pad8)") (class "Default")
      (node (ref "U1") (pin "8") (pinfunction "PB09(AIN3/SER4:1/TC4:1)_8") (pintype "bidirectional"))
    )
    (net (code "82") (name "unconnected-(U1-PB10(SER4:2+)-Pad19)") (class "Default")
      (node (ref "U1") (pin "19") (pinfunction "PB10(SER4:2+)_19") (pintype "bidirectional"))
    )
    (net (code "83") (name "unconnected-(U1-PB11(SER4:3+)-Pad20)") (class "Default")
      (node (ref "U1") (pin "20") (pinfunction "PB11(SER4:3+)_20") (pintype "bidirectional"))
    )
    (net (code "84") (name "unconnected-(U1-PB22(SER5:2+)-Pad37)") (class "Default")
      (node (ref "U1") (pin "37") (pinfunction "PB22(SER5:2+)_37") (pintype "bidirectional"))
    )
    (net (code "85") (name "unconnected-(X2-Pad4)") (class "Default")
      (node (ref "X2") (pin "4") (pinfunction "4_4") (pintype "passive"))
    )
  )
)
